# Sheet3.net
KiCad netlist of a schematic drawn in Altium Designer
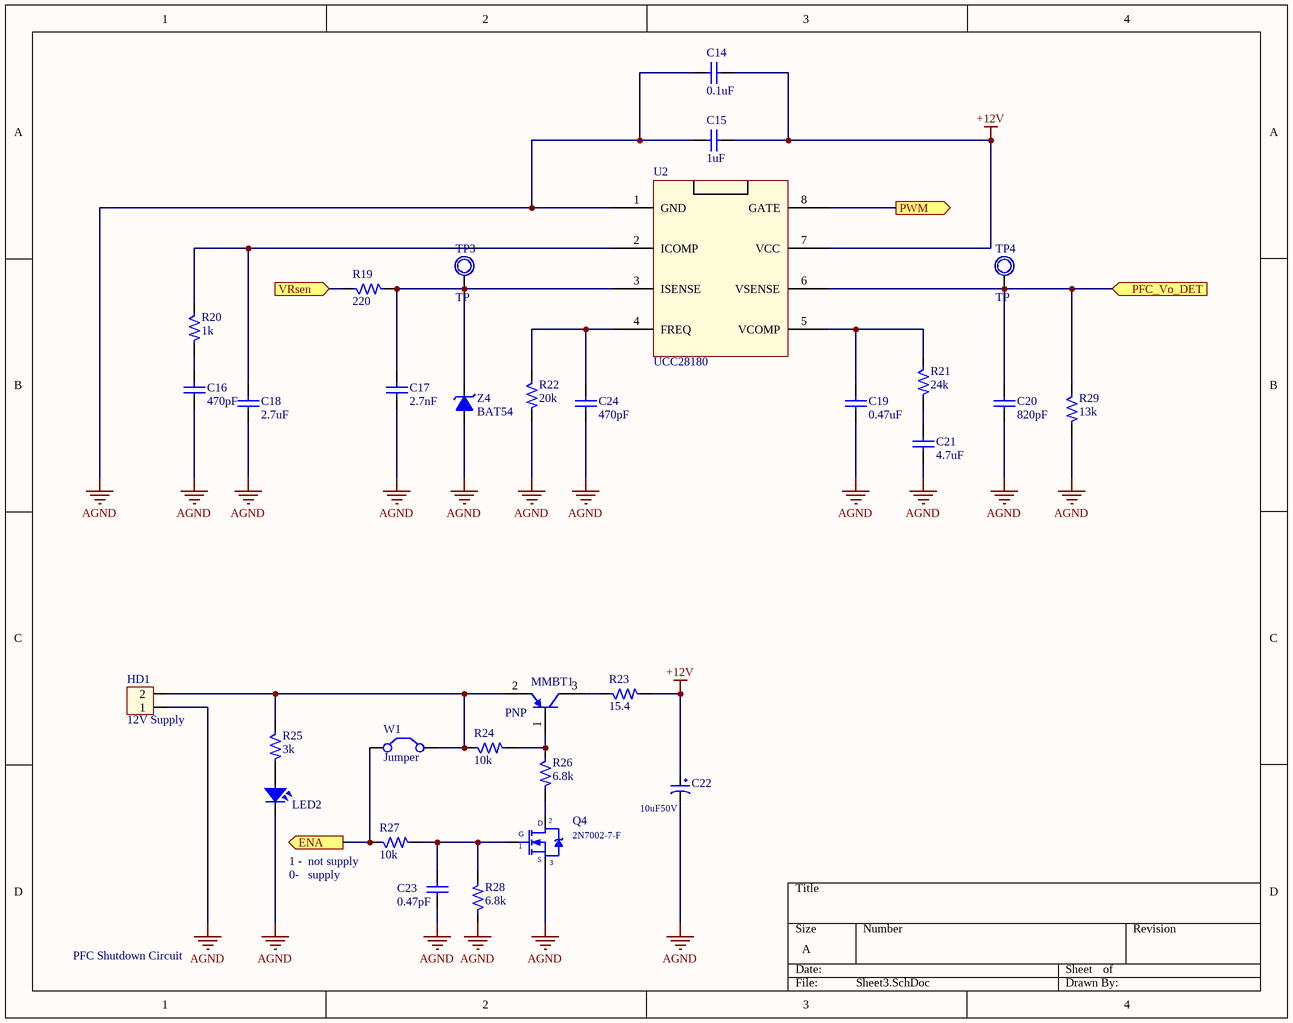
[diagram p0: Sheet3.SchDoc]

(export (version "E")
  (design (tool "Eeschema 10.0.6"))
  (components
    (comp (ref "C14")
      (value "0.1uF")
      (footprint "SM-CAP-0805")
      (description "Capacitor (Semiconductor SIM Model)")
      (fields (field (name "PUBLISHER") "Altium Limited"))
      (libsource (lib "syhaunguyen") (part "Cap Semi_3"))
    )
    (comp (ref "C15")
      (value "1uF")
      (footprint "Cap 3228")
      (description "Capacitor (Semiconductor SIM Model)")
      (fields (field (name "PUBLISHER") "Altium Limited"))
      (libsource (lib "syhaunguyen") (part "Cap Semi_3"))
    )
    (comp (ref "C16")
      (value "470pF")
      (footprint "SM-CAP-0805")
      (description "Capacitor (Semiconductor SIM Model)")
      (fields (field (name "PUBLISHER") "Altium Limited"))
      (libsource (lib "syhaunguyen") (part "Cap Semi_3"))
    )
    (comp (ref "C17")
      (value "2.7nF")
      (footprint "SM-CAP-0805")
      (description "Capacitor (Semiconductor SIM Model)")
      (fields (field (name "PUBLISHER") "Altium Limited"))
      (libsource (lib "syhaunguyen") (part "Cap Semi_3"))
    )
    (comp (ref "C18")
      (value "2.7uF")
      (footprint "SM-CAP-0805")
      (description "Capacitor (Semiconductor SIM Model)")
      (fields (field (name "PUBLISHER") "Altium Limited"))
      (libsource (lib "syhaunguyen") (part "Cap Semi_3"))
    )
    (comp (ref "C19")
      (value "0.47uF")
      (footprint "SM-CAP-0805")
      (description "Capacitor (Semiconductor SIM Model)")
      (fields (field (name "PUBLISHER") "Altium Limited"))
      (libsource (lib "syhaunguyen") (part "Cap Semi_3"))
    )
    (comp (ref "C20")
      (value "820pF")
      (footprint "SM-CAP-0805")
      (description "Capacitor (Semiconductor SIM Model)")
      (fields (field (name "PUBLISHER") "Altium Limited"))
      (libsource (lib "syhaunguyen") (part "Cap Semi_3"))
    )
    (comp (ref "C21")
      (value "4.7uF")
      (footprint "SM-CAP-0805")
      (description "Capacitor (Semiconductor SIM Model)")
      (fields (field (name "PUBLISHER") "Altium Limited"))
      (libsource (lib "syhaunguyen") (part "Cap Semi_3"))
    )
    (comp (ref "C22")
      (value "10uF50V")
      (footprint "CAP-ALU-SMD-4.5x5x1.4")
      (description "Cap 10000uF/63V")
      (libsource (lib "syhaunguyen") (part "CP9"))
    )
    (comp (ref "C23")
      (value "0.47pF")
      (footprint "SM-CAP-0805")
      (description "Capacitor (Semiconductor SIM Model)")
      (fields (field (name "PUBLISHER") "Altium Limited"))
      (libsource (lib "syhaunguyen") (part "Cap Semi_3"))
    )
    (comp (ref "C24")
      (value "470pF")
      (footprint "SM-CAP-0805")
      (description "Capacitor (Semiconductor SIM Model)")
      (fields (field (name "PUBLISHER") "Altium Limited"))
      (libsource (lib "syhaunguyen") (part "Cap Semi_3"))
    )
    (comp (ref "HD1")
      (value "12V Supply")
      (footprint "HED2")
      (description "Header 2 (Green)")
      (libsource (lib "syhaunguyen") (part "Hed2"))
    )
    (comp (ref "LED2")
      (value "LED")
      (footprint "SM-LED-0805-Green")
      (description "LED Single colour Green and Red")
      (libsource (lib "syhaunguyen") (part "LED"))
    )
    (comp (ref "MMBT1")
      (value "PNP")
      (footprint "SOT_23_P_transistor")
      (description "PNP Bipolar Transistor")
      (fields (field (name "PUBLISHER") "Altium Limited"))
      (libsource (lib "Miscellaneous Devices") (part "PNP"))
    )
    (comp (ref "Q4")
      (value "2N7002-7-F")
      (footprint "SOT_23_Mosfet")
      (description "MOSFET N - CHANNEL 500V - 0.75 - 8A - TO-220")
      (libsource (lib "syhaunguyen") (part "IRF840"))
    )
    (comp (ref "R19")
      (value "220")
      (footprint "SM-RES-0805")
      (description "Resistor 1/4W")
      (libsource (lib "syhaunguyen") (part "R"))
    )
    (comp (ref "R20")
      (value "1k")
      (footprint "SM-RES-0805")
      (description "Resistor 1/4W")
      (libsource (lib "syhaunguyen") (part "R"))
    )
    (comp (ref "R21")
      (value "24k")
      (footprint "SM-RES-0805")
      (description "Resistor 1/4W")
      (libsource (lib "syhaunguyen") (part "R"))
    )
    (comp (ref "R22")
      (value "20k")
      (footprint "SM-RES-0805")
      (description "Resistor 1/4W")
      (libsource (lib "syhaunguyen") (part "R"))
    )
    (comp (ref "R23")
      (value "15.4")
      (footprint "SM-RES-1206")
      (description "Resistor 1/4W")
      (libsource (lib "syhaunguyen") (part "R"))
    )
    (comp (ref "R24")
      (value "10k")
      (footprint "SM-RES-0805")
      (description "Resistor 1/4W")
      (libsource (lib "syhaunguyen") (part "R"))
    )
    (comp (ref "R25")
      (value "3k")
      (footprint "SM-RES-0805")
      (description "Resistor 1/4W")
      (libsource (lib "syhaunguyen") (part "R"))
    )
    (comp (ref "R26")
      (value "6.8k")
      (footprint "SM-RES-0805")
      (description "Resistor 1/4W")
      (libsource (lib "syhaunguyen") (part "R"))
    )
    (comp (ref "R27")
      (value "10k")
      (footprint "SM-RES-0805")
      (description "Resistor 1/4W")
      (libsource (lib "syhaunguyen") (part "R"))
    )
    (comp (ref "R28")
      (value "6.8k")
      (footprint "SM-RES-0805")
      (description "Resistor 1/4W")
      (libsource (lib "syhaunguyen") (part "R"))
    )
    (comp (ref "R29")
      (value "13k")
      (footprint "SM-RES-1206")
      (description "Resistor 1/4W")
      (libsource (lib "syhaunguyen") (part "R"))
    )
    (comp (ref "TP3")
      (value "TP")
      (footprint "TP1")
      (description "Test Point")
      (libsource (lib "syhaunguyen") (part "TP1"))
    )
    (comp (ref "TP4")
      (value "TP")
      (footprint "TP1")
      (description "Test Point")
      (libsource (lib "syhaunguyen") (part "TP1"))
    )
    (comp (ref "U2") (value "UCC28180") (footprint "UCC28180") (libsource (lib "UC3854") (part "UCC28180")))
    (comp (ref "W1")
      (value "Jumper")
      (footprint "JP2")
      (description "Jumper Wire")
      (fields (field (name "PUBLISHER") "Altium Limited"))
      (libsource (lib "Miscellaneous Devices") (part "Jumper"))
    )
    (comp (ref "Z4") (value "BAT54") (footprint "BZT52C15") (libsource (lib "syhaunguyen") (part "Zener")))
  )
  (nets
    (net (code "1") (name "+12V") (class "Default")
      (node (ref "C14") (pin "1") (pinfunction "1_1") (pintype "passive"))
      (node (ref "C15") (pin "1") (pinfunction "1_1") (pintype "passive"))
      (node (ref "C22") (pin "1") (pinfunction "1_1") (pintype "passive"))
      (node (ref "R23") (pin "2") (pinfunction "2_2") (pintype "passive"))
      (node (ref "U2") (pin "7") (pinfunction "VCC_7") (pintype "passive"))
    )
    (net (code "2") (name "/ENA") (class "Default")
      (node (ref "R27") (pin "1") (pinfunction "1_1") (pintype "passive"))
      (node (ref "W1") (pin "1") (pinfunction "C1_1") (pintype "passive"))
    )
    (net (code "3") (name "/PFC_Vo_DET") (class "Default")
      (node (ref "C20") (pin "2") (pinfunction "2_2") (pintype "passive"))
      (node (ref "R29") (pin "1") (pinfunction "1_1") (pintype "passive"))
      (node (ref "TP4") (pin "1") (pinfunction "1_1") (pintype "passive"))
      (node (ref "U2") (pin "6") (pinfunction "VSENSE_6") (pintype "passive"))
    )
    (net (code "4") (name "/PWM") (class "Default")
      (node (ref "U2") (pin "8") (pinfunction "GATE_8") (pintype "passive"))
    )
    (net (code "5") (name "/VRsen") (class "Default")
      (node (ref "R19") (pin "1") (pinfunction "1_1") (pintype "passive"))
    )
    (net (code "6") (name "AGND") (class "Default")
      (node (ref "C14") (pin "2") (pinfunction "2_2") (pintype "passive"))
      (node (ref "C15") (pin "2") (pinfunction "2_2") (pintype "passive"))
      (node (ref "C16") (pin "1") (pinfunction "1_1") (pintype "passive"))
      (node (ref "C17") (pin "1") (pinfunction "1_1") (pintype "passive"))
      (node (ref "C18") (pin "1") (pinfunction "1_1") (pintype "passive"))
      (node (ref "C19") (pin "1") (pinfunction "1_1") (pintype "passive"))
      (node (ref "C20") (pin "1") (pinfunction "1_1") (pintype "passive"))
      (node (ref "C21") (pin "1") (pinfunction "1_1") (pintype "passive"))
      (node (ref "C22") (pin "2") (pinfunction "2_2") (pintype "passive"))
      (node (ref "C23") (pin "1") (pinfunction "1_1") (pintype "passive"))
      (node (ref "C24") (pin "1") (pinfunction "1_1") (pintype "passive"))
      (node (ref "HD1") (pin "1") (pinfunction "1_1") (pintype "passive"))
      (node (ref "LED2") (pin "2") (pinfunction "2_2") (pintype "passive"))
      (node (ref "Q4") (pin "1") (pinfunction "G_1") (pintype "passive"))
      (node (ref "R22") (pin "2") (pinfunction "2_2") (pintype "passive"))
      (node (ref "R28") (pin "1") (pinfunction "1_1") (pintype "passive"))
      (node (ref "R29") (pin "2") (pinfunction "2_2") (pintype "passive"))
      (node (ref "U2") (pin "1") (pinfunction "GND_1") (pintype "passive"))
      (node (ref "Z4") (pin "1") (pinfunction "A_1") (pintype "passive"))
    )
    (net (code "7") (name "Net-(C16-Pad2)") (class "Default")
      (node (ref "C16") (pin "2") (pinfunction "2_2") (pintype "passive"))
      (node (ref "R20") (pin "2") (pinfunction "2_2") (pintype "passive"))
    )
    (net (code "8") (name "Net-(C21-Pad2)") (class "Default")
      (node (ref "C21") (pin "2") (pinfunction "2_2") (pintype "passive"))
      (node (ref "R21") (pin "2") (pinfunction "2_2") (pintype "passive"))
    )
    (net (code "9") (name "Net-(LED2-Pad1)") (class "Default")
      (node (ref "LED2") (pin "1") (pinfunction "1_1") (pintype "passive"))
      (node (ref "R25") (pin "2") (pinfunction "2_2") (pintype "passive"))
    )
    (net (code "10") (name "Net-(MMBT1-B)") (class "Default")
      (node (ref "MMBT1") (pin "1") (pinfunction "B_1") (pintype "passive"))
      (node (ref "R24") (pin "2") (pinfunction "2_2") (pintype "passive"))
      (node (ref "R26") (pin "1") (pinfunction "1_1") (pintype "passive"))
    )
    (net (code "11") (name "Net-(MMBT1-C)") (class "Default")
      (node (ref "MMBT1") (pin "3") (pinfunction "C_3") (pintype "passive"))
      (node (ref "R23") (pin "1") (pinfunction "1_1") (pintype "passive"))
    )
    (net (code "12") (name "Net-(MMBT1-E)") (class "Default")
      (node (ref "HD1") (pin "2") (pinfunction "2_2") (pintype "passive"))
      (node (ref "MMBT1") (pin "2") (pinfunction "E_2") (pintype "passive"))
      (node (ref "R24") (pin "1") (pinfunction "1_1") (pintype "passive"))
      (node (ref "R25") (pin "1") (pinfunction "1_1") (pintype "passive"))
      (node (ref "W1") (pin "2") (pinfunction "C2_2") (pintype "passive"))
    )
    (net (code "13") (name "Net-(Q4-D)") (class "Default")
      (node (ref "C23") (pin "2") (pinfunction "2_2") (pintype "passive"))
      (node (ref "Q4") (pin "2") (pinfunction "D_2") (pintype "passive"))
      (node (ref "R27") (pin "2") (pinfunction "2_2") (pintype "passive"))
      (node (ref "R28") (pin "2") (pinfunction "2_2") (pintype "passive"))
    )
    (net (code "14") (name "Net-(Q4-S)") (class "Default")
      (node (ref "Q4") (pin "3") (pinfunction "S_3") (pintype "passive"))
      (node (ref "R26") (pin "2") (pinfunction "2_2") (pintype "passive"))
    )
    (net (code "15") (name "Net-(U2-FREQ)") (class "Default")
      (node (ref "C24") (pin "2") (pinfunction "2_2") (pintype "passive"))
      (node (ref "R22") (pin "1") (pinfunction "1_1") (pintype "passive"))
      (node (ref "U2") (pin "4") (pinfunction "FREQ_4") (pintype "passive"))
    )
    (net (code "16") (name "Net-(U2-ICOMP)") (class "Default")
      (node (ref "C18") (pin "2") (pinfunction "2_2") (pintype "passive"))
      (node (ref "R20") (pin "1") (pinfunction "1_1") (pintype "passive"))
      (node (ref "U2") (pin "2") (pinfunction "ICOMP_2") (pintype "passive"))
    )
    (net (code "17") (name "Net-(U2-ISENSE)") (class "Default")
      (node (ref "C17") (pin "2") (pinfunction "2_2") (pintype "passive"))
      (node (ref "R19") (pin "2") (pinfunction "2_2") (pintype "passive"))
      (node (ref "TP3") (pin "1") (pinfunction "1_1") (pintype "passive"))
      (node (ref "U2") (pin "3") (pinfunction "ISENSE_3") (pintype "passive"))
      (node (ref "Z4") (pin "2") (pinfunction "K_2") (pintype "passive"))
    )
    (net (code "18") (name "Net-(U2-VCOMP)") (class "Default")
      (node (ref "C19") (pin "2") (pinfunction "2_2") (pintype "passive"))
      (node (ref "R21") (pin "1") (pinfunction "1_1") (pintype "passive"))
      (node (ref "U2") (pin "5") (pinfunction "VCOMP_5") (pintype "passive"))
    )
  )
)
